# DACv4-Controller.net
KiCad netlist of a schematic drawn in EAGLE
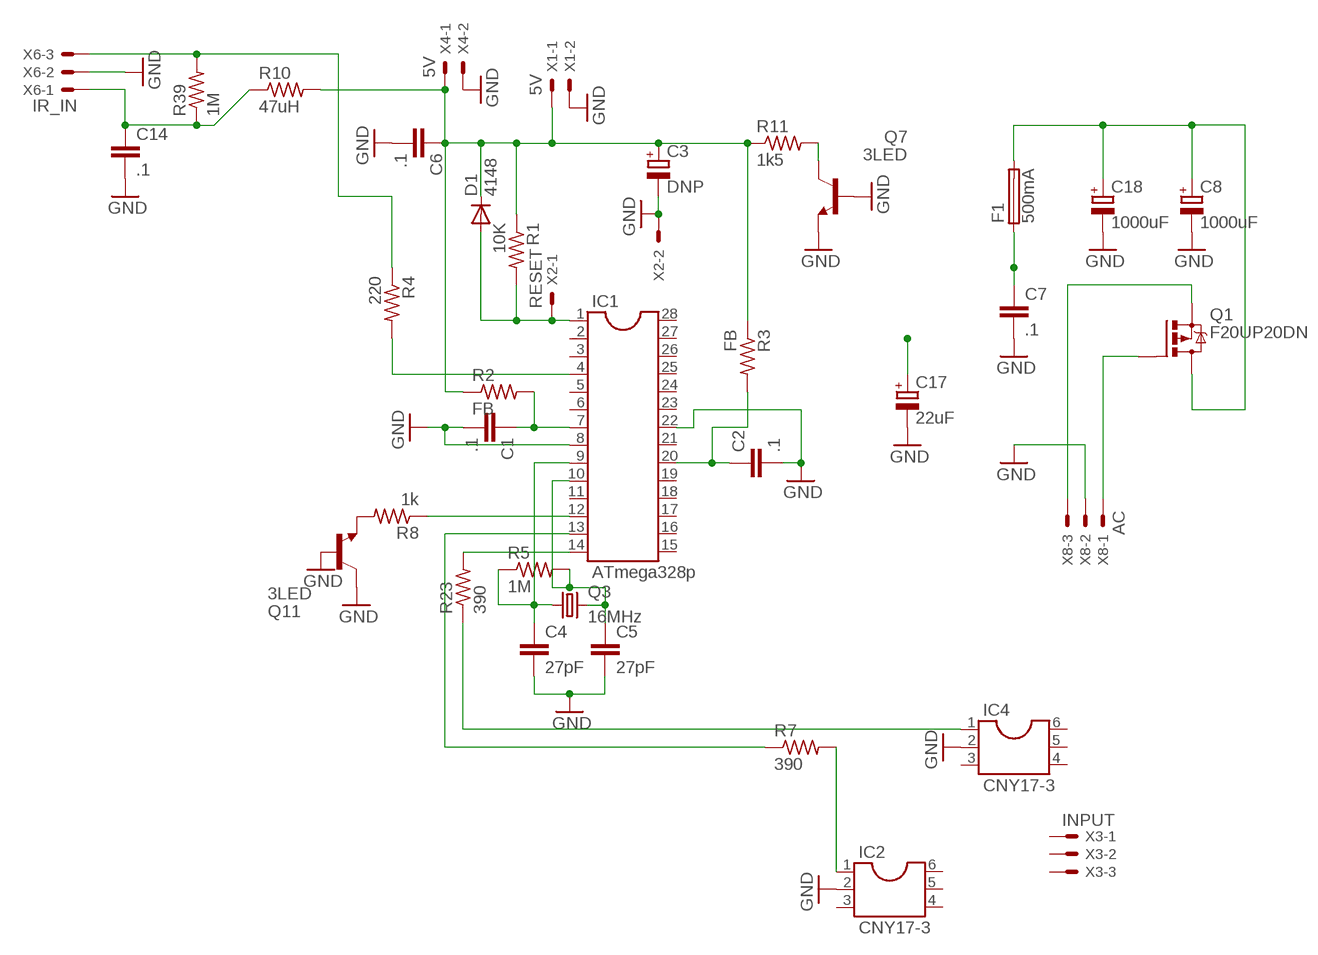
[diagram p0: schematic, sheet 1]

(export (version "E")
  (design (tool "Eeschema 10.0.6"))
  (components
    (comp (ref "C1")
      (value ".1")
      (footprint "eagle-import:C1210K")
      (libsource (lib "eagle-import") (part "C-EUC1210K"))
    )
    (comp (ref "C2")
      (value ".1")
      (footprint "eagle-import:C1210K")
      (libsource (lib "eagle-import") (part "C-EUC1210K"))
    )
    (comp (ref "C3")
      (value "DNP")
      (footprint "eagle-import:E3,5-10")
      (libsource (lib "eagle-import") (part "CPOL-EUE3.5-10"))
    )
    (comp (ref "C4")
      (value "27pF")
      (footprint "eagle-import:C1210K")
      (libsource (lib "eagle-import") (part "C-EUC1210K"))
    )
    (comp (ref "C5")
      (value "27pF")
      (footprint "eagle-import:C1210K")
      (libsource (lib "eagle-import") (part "C-EUC1210K"))
    )
    (comp (ref "C6")
      (value ".1")
      (footprint "eagle-import:C1210K")
      (libsource (lib "eagle-import") (part "C-EUC1210K"))
    )
    (comp (ref "C7")
      (value ".1")
      (footprint "eagle-import:C1210K")
      (libsource (lib "eagle-import") (part "C-EUC1210K"))
    )
    (comp (ref "C8")
      (value "1000uF")
      (footprint "eagle-import:E5-13")
      (libsource (lib "eagle-import") (part "CPOL-EUE5-13"))
    )
    (comp (ref "C14")
      (value ".1")
      (footprint "eagle-import:C1210K")
      (libsource (lib "eagle-import") (part "C-EUC1210K"))
    )
    (comp (ref "C17")
      (value "22uF")
      (footprint "eagle-import:E3,5-10")
      (libsource (lib "eagle-import") (part "CPOL-EUE3.5-10"))
    )
    (comp (ref "C18")
      (value "1000uF")
      (footprint "eagle-import:E5-13")
      (libsource (lib "eagle-import") (part "CPOL-EUE5-13"))
    )
    (comp (ref "D1")
      (value "4148")
      (footprint "eagle-import:DO35-7")
      (libsource (lib "eagle-import") (part "1N4148DO35-7"))
    )
    (comp (ref "F1")
      (value "500mA")
      (footprint "eagle-import:19560")
      (fields (field (name "MPN") "56000001009"))
      (libsource (lib "eagle-import") (part "19560"))
    )
    (comp (ref "IC1")
      (value "ATmega328p")
      (footprint "eagle-import:DIL28-3")
      (libsource (lib "eagle-import") (part "DIL28-3"))
    )
    (comp (ref "IC2")
      (value "CNY17-3")
      (footprint "eagle-import:DIL06")
      (libsource (lib "eagle-import") (part "DIL6"))
    )
    (comp (ref "IC4")
      (value "CNY17-3")
      (footprint "eagle-import:DIL06")
      (libsource (lib "eagle-import") (part "DIL6"))
    )
    (comp (ref "Q1")
      (value "F20UP20DN")
      (footprint "eagle-import:TO220BV")
      (libsource (lib "eagle-import") (part "IRF9530"))
    )
    (comp (ref "Q3")
      (value "16MHz")
      (footprint "eagle-import:HC49_S")
      (libsource (lib "eagle-import") (part "CRYSTALHC49S"))
    )
    (comp (ref "Q7")
      (value "3LED")
      (footprint "eagle-import:TO92-EBC")
      (libsource (lib "eagle-import") (part "BC546A"))
    )
    (comp (ref "Q11")
      (value "3LED")
      (footprint "eagle-import:TO92-EBC")
      (libsource (lib "eagle-import") (part "BC546A"))
    )
    (comp (ref "R1")
      (value "10K")
      (footprint "eagle-import:0309_10")
      (libsource (lib "eagle-import") (part "R-US_0309/10"))
    )
    (comp (ref "R2")
      (value "FB")
      (footprint "eagle-import:0309_10")
      (libsource (lib "eagle-import") (part "R-US_0309/10"))
    )
    (comp (ref "R3")
      (value "FB")
      (footprint "eagle-import:0309_12")
      (libsource (lib "eagle-import") (part "R-US_0309/12"))
    )
    (comp (ref "R4")
      (value "220")
      (footprint "eagle-import:0309_12")
      (libsource (lib "eagle-import") (part "R-US_0309/12"))
    )
    (comp (ref "R5")
      (value "1M")
      (footprint "eagle-import:0309V")
      (libsource (lib "eagle-import") (part "R-US_0309/V"))
    )
    (comp (ref "R7")
      (value "390")
      (footprint "eagle-import:0309_10")
      (libsource (lib "eagle-import") (part "R-US_0309/10"))
    )
    (comp (ref "R8")
      (value "1k")
      (footprint "eagle-import:0204_7")
      (libsource (lib "eagle-import") (part "R-US_0204/7"))
    )
    (comp (ref "R10")
      (value "47uH")
      (footprint "eagle-import:0309_10")
      (libsource (lib "eagle-import") (part "R-US_0309/10"))
    )
    (comp (ref "R11")
      (value "1k5")
      (footprint "eagle-import:0309_12")
      (libsource (lib "eagle-import") (part "R-US_0309/12"))
    )
    (comp (ref "R23")
      (value "390")
      (footprint "eagle-import:0309_10")
      (libsource (lib "eagle-import") (part "R-US_0309/10"))
    )
    (comp (ref "R39")
      (value "1M")
      (footprint "eagle-import:0309_10")
      (libsource (lib "eagle-import") (part "R-US_0309/10"))
    )
    (comp (ref "X1")
      (value "5V")
      (footprint "eagle-import:22-23-2021")
      (fields (field (name "MF") "MOLEX") (field (name "MPN") "22-23-2021"))
      (libsource (lib "eagle-import") (part "22-23-2021"))
    )
    (comp (ref "X2")
      (value "RESET")
      (footprint "eagle-import:22-23-2021")
      (fields (field (name "MF") "MOLEX") (field (name "MPN") "22-23-2021"))
      (libsource (lib "eagle-import") (part "22-23-2021"))
    )
    (comp (ref "X3")
      (value "INPUT")
      (footprint "eagle-import:22-23-2031")
      (fields (field (name "MF") "MOLEX") (field (name "MPN") "22-23-2031"))
      (libsource (lib "eagle-import") (part "22-23-2031"))
    )
    (comp (ref "X4")
      (value "5V")
      (footprint "eagle-import:22-23-2021")
      (fields (field (name "MF") "MOLEX") (field (name "MPN") "22-23-2021"))
      (libsource (lib "eagle-import") (part "22-23-2021"))
    )
    (comp (ref "X6")
      (value "IR_IN")
      (footprint "eagle-import:22-23-2031")
      (fields (field (name "MF") "MOLEX") (field (name "MPN") "22-23-2031"))
      (libsource (lib "eagle-import") (part "22-23-2031"))
    )
    (comp (ref "X8")
      (value "AC")
      (footprint "eagle-import:22-23-2031")
      (fields (field (name "MF") "MOLEX") (field (name "MPN") "22-23-2031"))
      (libsource (lib "eagle-import") (part "22-23-2031"))
    )
  )
  (nets
    (net (code "1") (name "GND") (class "Default")
      (node (ref "C1") (pin "2") (pinfunction "2_2") (pintype "passive"))
      (node (ref "C14") (pin "2") (pinfunction "2_2") (pintype "passive"))
      (node (ref "C17") (pin "-") (pinfunction "-_-") (pintype "passive"))
      (node (ref "C18") (pin "-") (pinfunction "-_-") (pintype "passive"))
      (node (ref "C2") (pin "2") (pinfunction "2_2") (pintype "passive"))
      (node (ref "C3") (pin "-") (pinfunction "-_-") (pintype "passive"))
      (node (ref "C4") (pin "2") (pinfunction "2_2") (pintype "passive"))
      (node (ref "C5") (pin "2") (pinfunction "2_2") (pintype "passive"))
      (node (ref "C6") (pin "2") (pinfunction "2_2") (pintype "passive"))
      (node (ref "C7") (pin "2") (pinfunction "2_2") (pintype "passive"))
      (node (ref "C8") (pin "-") (pinfunction "-_-") (pintype "passive"))
      (node (ref "IC1") (pin "22") (pinfunction "22_22") (pintype "passive"))
      (node (ref "IC1") (pin "8") (pinfunction "8_8") (pintype "passive"))
      (node (ref "IC2") (pin "2") (pinfunction "2_2") (pintype "passive"))
      (node (ref "IC4") (pin "2") (pinfunction "2_2") (pintype "passive"))
      (node (ref "Q11") (pin "B") (pinfunction "B_B") (pintype "passive"))
      (node (ref "Q11") (pin "C") (pinfunction "C_C") (pintype "passive"))
      (node (ref "Q7") (pin "B") (pinfunction "B_B") (pintype "passive"))
      (node (ref "Q7") (pin "E") (pinfunction "E_E") (pintype "passive"))
      (node (ref "X1") (pin "2") (pinfunction "S_2") (pintype "passive"))
      (node (ref "X2") (pin "2") (pinfunction "S_2") (pintype "passive"))
      (node (ref "X4") (pin "2") (pinfunction "S_2") (pintype "passive"))
      (node (ref "X6") (pin "2") (pinfunction "S_2") (pintype "passive"))
      (node (ref "X8") (pin "2") (pinfunction "S_2") (pintype "passive"))
    )
    (net (code "2") (name "Net-(C1-Pad1)") (class "Default")
      (node (ref "C1") (pin "1") (pinfunction "1_1") (pintype "passive"))
      (node (ref "IC1") (pin "7") (pinfunction "7_7") (pintype "passive"))
      (node (ref "R2") (pin "2") (pinfunction "2_2") (pintype "passive"))
    )
    (net (code "3") (name "Net-(C2-Pad1)") (class "Default")
      (node (ref "C2") (pin "1") (pinfunction "1_1") (pintype "passive"))
      (node (ref "IC1") (pin "20") (pinfunction "20_20") (pintype "passive"))
      (node (ref "R3") (pin "2") (pinfunction "2_2") (pintype "passive"))
    )
    (net (code "4") (name "Net-(C4-Pad1)") (class "Default")
      (node (ref "C4") (pin "1") (pinfunction "1_1") (pintype "passive"))
      (node (ref "IC1") (pin "9") (pinfunction "9_9") (pintype "passive"))
      (node (ref "Q3") (pin "1") (pinfunction "1_1") (pintype "passive"))
      (node (ref "R5") (pin "1") (pinfunction "1_1") (pintype "passive"))
    )
    (net (code "5") (name "Net-(C5-Pad1)") (class "Default")
      (node (ref "C5") (pin "1") (pinfunction "1_1") (pintype "passive"))
      (node (ref "IC1") (pin "10") (pinfunction "10_10") (pintype "passive"))
      (node (ref "Q3") (pin "2") (pinfunction "2_2") (pintype "passive"))
      (node (ref "R5") (pin "2") (pinfunction "2_2") (pintype "passive"))
    )
    (net (code "6") (name "Net-(C7-Pad1)") (class "Default")
      (node (ref "C7") (pin "1") (pinfunction "1_1") (pintype "passive"))
      (node (ref "F1") (pin "1") (pinfunction "1_1") (pintype "passive"))
    )
    (net (code "7") (name "Net-(C18-Pad+)") (class "Default")
      (node (ref "C18") (pin "+") (pinfunction "+_+") (pintype "passive"))
      (node (ref "C8") (pin "+") (pinfunction "+_+") (pintype "passive"))
      (node (ref "F1") (pin "2") (pinfunction "2_2") (pintype "passive"))
      (node (ref "Q1") (pin "D") (pinfunction "D_D") (pintype "passive"))
    )
    (net (code "8") (name "Net-(IC1-Pad4)") (class "Default")
      (node (ref "IC1") (pin "4") (pinfunction "4_4") (pintype "passive"))
      (node (ref "R4") (pin "2") (pinfunction "2_2") (pintype "passive"))
    )
    (net (code "9") (name "Net-(IC1-Pad12)") (class "Default")
      (node (ref "IC1") (pin "12") (pinfunction "12_12") (pintype "passive"))
      (node (ref "R8") (pin "1") (pinfunction "1_1") (pintype "passive"))
    )
    (net (code "10") (name "Net-(IC1-Pad13)") (class "Default")
      (node (ref "IC1") (pin "13") (pinfunction "13_13") (pintype "passive"))
      (node (ref "R7") (pin "1") (pinfunction "1_1") (pintype "passive"))
    )
    (net (code "11") (name "Net-(IC1-Pad14)") (class "Default")
      (node (ref "IC1") (pin "14") (pinfunction "14_14") (pintype "passive"))
      (node (ref "R23") (pin "2") (pinfunction "2_2") (pintype "passive"))
    )
    (net (code "12") (name "Net-(IC2-Pad1)") (class "Default")
      (node (ref "IC2") (pin "1") (pinfunction "1_1") (pintype "passive"))
      (node (ref "R7") (pin "2") (pinfunction "2_2") (pintype "passive"))
    )
    (net (code "13") (name "Net-(IC4-Pad1)") (class "Default")
      (node (ref "IC4") (pin "1") (pinfunction "1_1") (pintype "passive"))
      (node (ref "R23") (pin "1") (pinfunction "1_1") (pintype "passive"))
    )
    (net (code "14") (name "Net-(Q7-PadC)") (class "Default")
      (node (ref "Q7") (pin "C") (pinfunction "C_C") (pintype "passive"))
      (node (ref "R11") (pin "2") (pinfunction "2_2") (pintype "passive"))
    )
    (net (code "15") (name "Net-(Q11-PadE)") (class "Default")
      (node (ref "Q11") (pin "E") (pinfunction "E_E") (pintype "passive"))
      (node (ref "R8") (pin "2") (pinfunction "2_2") (pintype "passive"))
    )
    (net (code "16") (name "Net-(X1A-S)") (class "Default")
      (node (ref "C3") (pin "+") (pinfunction "+_+") (pintype "passive"))
      (node (ref "C6") (pin "1") (pinfunction "1_1") (pintype "passive"))
      (node (ref "D1") (pin "C") (pinfunction "C_C") (pintype "passive"))
      (node (ref "R1") (pin "1") (pinfunction "1_1") (pintype "passive"))
      (node (ref "R10") (pin "2") (pinfunction "2_2") (pintype "passive"))
      (node (ref "R11") (pin "1") (pinfunction "1_1") (pintype "passive"))
      (node (ref "R2") (pin "1") (pinfunction "1_1") (pintype "passive"))
      (node (ref "R3") (pin "1") (pinfunction "1_1") (pintype "passive"))
      (node (ref "X1") (pin "1") (pinfunction "S_1") (pintype "passive"))
      (node (ref "X4") (pin "1") (pinfunction "S_1") (pintype "passive"))
    )
    (net (code "17") (name "Net-(X2A-S)") (class "Default")
      (node (ref "D1") (pin "A") (pinfunction "A_A") (pintype "passive"))
      (node (ref "IC1") (pin "1") (pinfunction "1_1") (pintype "passive"))
      (node (ref "R1") (pin "2") (pinfunction "2_2") (pintype "passive"))
      (node (ref "X2") (pin "1") (pinfunction "S_1") (pintype "passive"))
    )
    (net (code "18") (name "Net-(X6A-S)") (class "Default")
      (node (ref "C14") (pin "1") (pinfunction "1_1") (pintype "passive"))
      (node (ref "R10") (pin "1") (pinfunction "1_1") (pintype "passive"))
      (node (ref "R39") (pin "1") (pinfunction "1_1") (pintype "passive"))
      (node (ref "X6") (pin "1") (pinfunction "S_1") (pintype "passive"))
    )
    (net (code "19") (name "Net-(X6C-S)") (class "Default")
      (node (ref "R39") (pin "2") (pinfunction "2_2") (pintype "passive"))
      (node (ref "R4") (pin "1") (pinfunction "1_1") (pintype "passive"))
      (node (ref "X6") (pin "3") (pinfunction "S_3") (pintype "passive"))
    )
    (net (code "20") (name "Net-(X8A-S)") (class "Default")
      (node (ref "Q1") (pin "G") (pinfunction "G_G") (pintype "passive"))
      (node (ref "X8") (pin "1") (pinfunction "S_1") (pintype "passive"))
    )
    (net (code "21") (name "Net-(X8C-S)") (class "Default")
      (node (ref "Q1") (pin "S") (pinfunction "S_S") (pintype "passive"))
      (node (ref "X8") (pin "3") (pinfunction "S_3") (pintype "passive"))
    )
    (net (code "22") (name "unconnected-(C17-Pad+)") (class "Default")
      (node (ref "C17") (pin "+") (pinfunction "+_+") (pintype "passive"))
    )
    (net (code "23") (name "unconnected-(IC1-Pad2)") (class "Default")
      (node (ref "IC1") (pin "2") (pinfunction "2_2") (pintype "passive"))
    )
    (net (code "24") (name "unconnected-(IC1-Pad3)") (class "Default")
      (node (ref "IC1") (pin "3") (pinfunction "3_3") (pintype "passive"))
    )
    (net (code "25") (name "unconnected-(IC1-Pad5)") (class "Default")
      (node (ref "IC1") (pin "5") (pinfunction "5_5") (pintype "passive"))
    )
    (net (code "26") (name "unconnected-(IC1-Pad6)") (class "Default")
      (node (ref "IC1") (pin "6") (pinfunction "6_6") (pintype "passive"))
    )
    (net (code "27") (name "unconnected-(IC1-Pad11)") (class "Default")
      (node (ref "IC1") (pin "11") (pinfunction "11_11") (pintype "passive"))
    )
    (net (code "28") (name "unconnected-(IC1-Pad15)") (class "Default")
      (node (ref "IC1") (pin "15") (pinfunction "15_15") (pintype "passive"))
    )
    (net (code "29") (name "unconnected-(IC1-Pad16)") (class "Default")
      (node (ref "IC1") (pin "16") (pinfunction "16_16") (pintype "passive"))
    )
    (net (code "30") (name "unconnected-(IC1-Pad17)") (class "Default")
      (node (ref "IC1") (pin "17") (pinfunction "17_17") (pintype "passive"))
    )
    (net (code "31") (name "unconnected-(IC1-Pad18)") (class "Default")
      (node (ref "IC1") (pin "18") (pinfunction "18_18") (pintype "passive"))
    )
    (net (code "32") (name "unconnected-(IC1-Pad19)") (class "Default")
      (node (ref "IC1") (pin "19") (pinfunction "19_19") (pintype "passive"))
    )
    (net (code "33") (name "unconnected-(IC1-Pad21)") (class "Default")
      (node (ref "IC1") (pin "21") (pinfunction "21_21") (pintype "passive"))
    )
    (net (code "34") (name "unconnected-(IC1-Pad23)") (class "Default")
      (node (ref "IC1") (pin "23") (pinfunction "23_23") (pintype "passive"))
    )
    (net (code "35") (name "unconnected-(IC1-Pad24)") (class "Default")
      (node (ref "IC1") (pin "24") (pinfunction "24_24") (pintype "passive"))
    )
    (net (code "36") (name "unconnected-(IC1-Pad25)") (class "Default")
      (node (ref "IC1") (pin "25") (pinfunction "25_25") (pintype "passive"))
    )
    (net (code "37") (name "unconnected-(IC1-Pad26)") (class "Default")
      (node (ref "IC1") (pin "26") (pinfunction "26_26") (pintype "passive"))
    )
    (net (code "38") (name "unconnected-(IC1-Pad27)") (class "Default")
      (node (ref "IC1") (pin "27") (pinfunction "27_27") (pintype "passive"))
    )
    (net (code "39") (name "unconnected-(IC1-Pad28)") (class "Default")
      (node (ref "IC1") (pin "28") (pinfunction "28_28") (pintype "passive"))
    )
    (net (code "40") (name "unconnected-(IC2-Pad3)") (class "Default")
      (node (ref "IC2") (pin "3") (pinfunction "3_3") (pintype "passive"))
    )
    (net (code "41") (name "unconnected-(IC2-Pad4)") (class "Default")
      (node (ref "IC2") (pin "4") (pinfunction "4_4") (pintype "passive"))
    )
    (net (code "42") (name "unconnected-(IC2-Pad5)") (class "Default")
      (node (ref "IC2") (pin "5") (pinfunction "5_5") (pintype "passive"))
    )
    (net (code "43") (name "unconnected-(IC2-Pad6)") (class "Default")
      (node (ref "IC2") (pin "6") (pinfunction "6_6") (pintype "passive"))
    )
    (net (code "44") (name "unconnected-(IC4-Pad3)") (class "Default")
      (node (ref "IC4") (pin "3") (pinfunction "3_3") (pintype "passive"))
    )
    (net (code "45") (name "unconnected-(IC4-Pad4)") (class "Default")
      (node (ref "IC4") (pin "4") (pinfunction "4_4") (pintype "passive"))
    )
    (net (code "46") (name "unconnected-(IC4-Pad5)") (class "Default")
      (node (ref "IC4") (pin "5") (pinfunction "5_5") (pintype "passive"))
    )
    (net (code "47") (name "unconnected-(IC4-Pad6)") (class "Default")
      (node (ref "IC4") (pin "6") (pinfunction "6_6") (pintype "passive"))
    )
    (net (code "48") (name "unconnected-(X3A-S-Pad1)") (class "Default")
      (node (ref "X3") (pin "1") (pinfunction "S_1") (pintype "passive"))
    )
    (net (code "49") (name "unconnected-(X3B-S-Pad2)") (class "Default")
      (node (ref "X3") (pin "2") (pinfunction "S_2") (pintype "passive"))
    )
    (net (code "50") (name "unconnected-(X3C-S-Pad3)") (class "Default")
      (node (ref "X3") (pin "3") (pinfunction "S_3") (pintype "passive"))
    )
  )
)
